# SCH_HackerCard_2024-08-18.net
KiCad netlist of a schematic drawn in EasyEDA
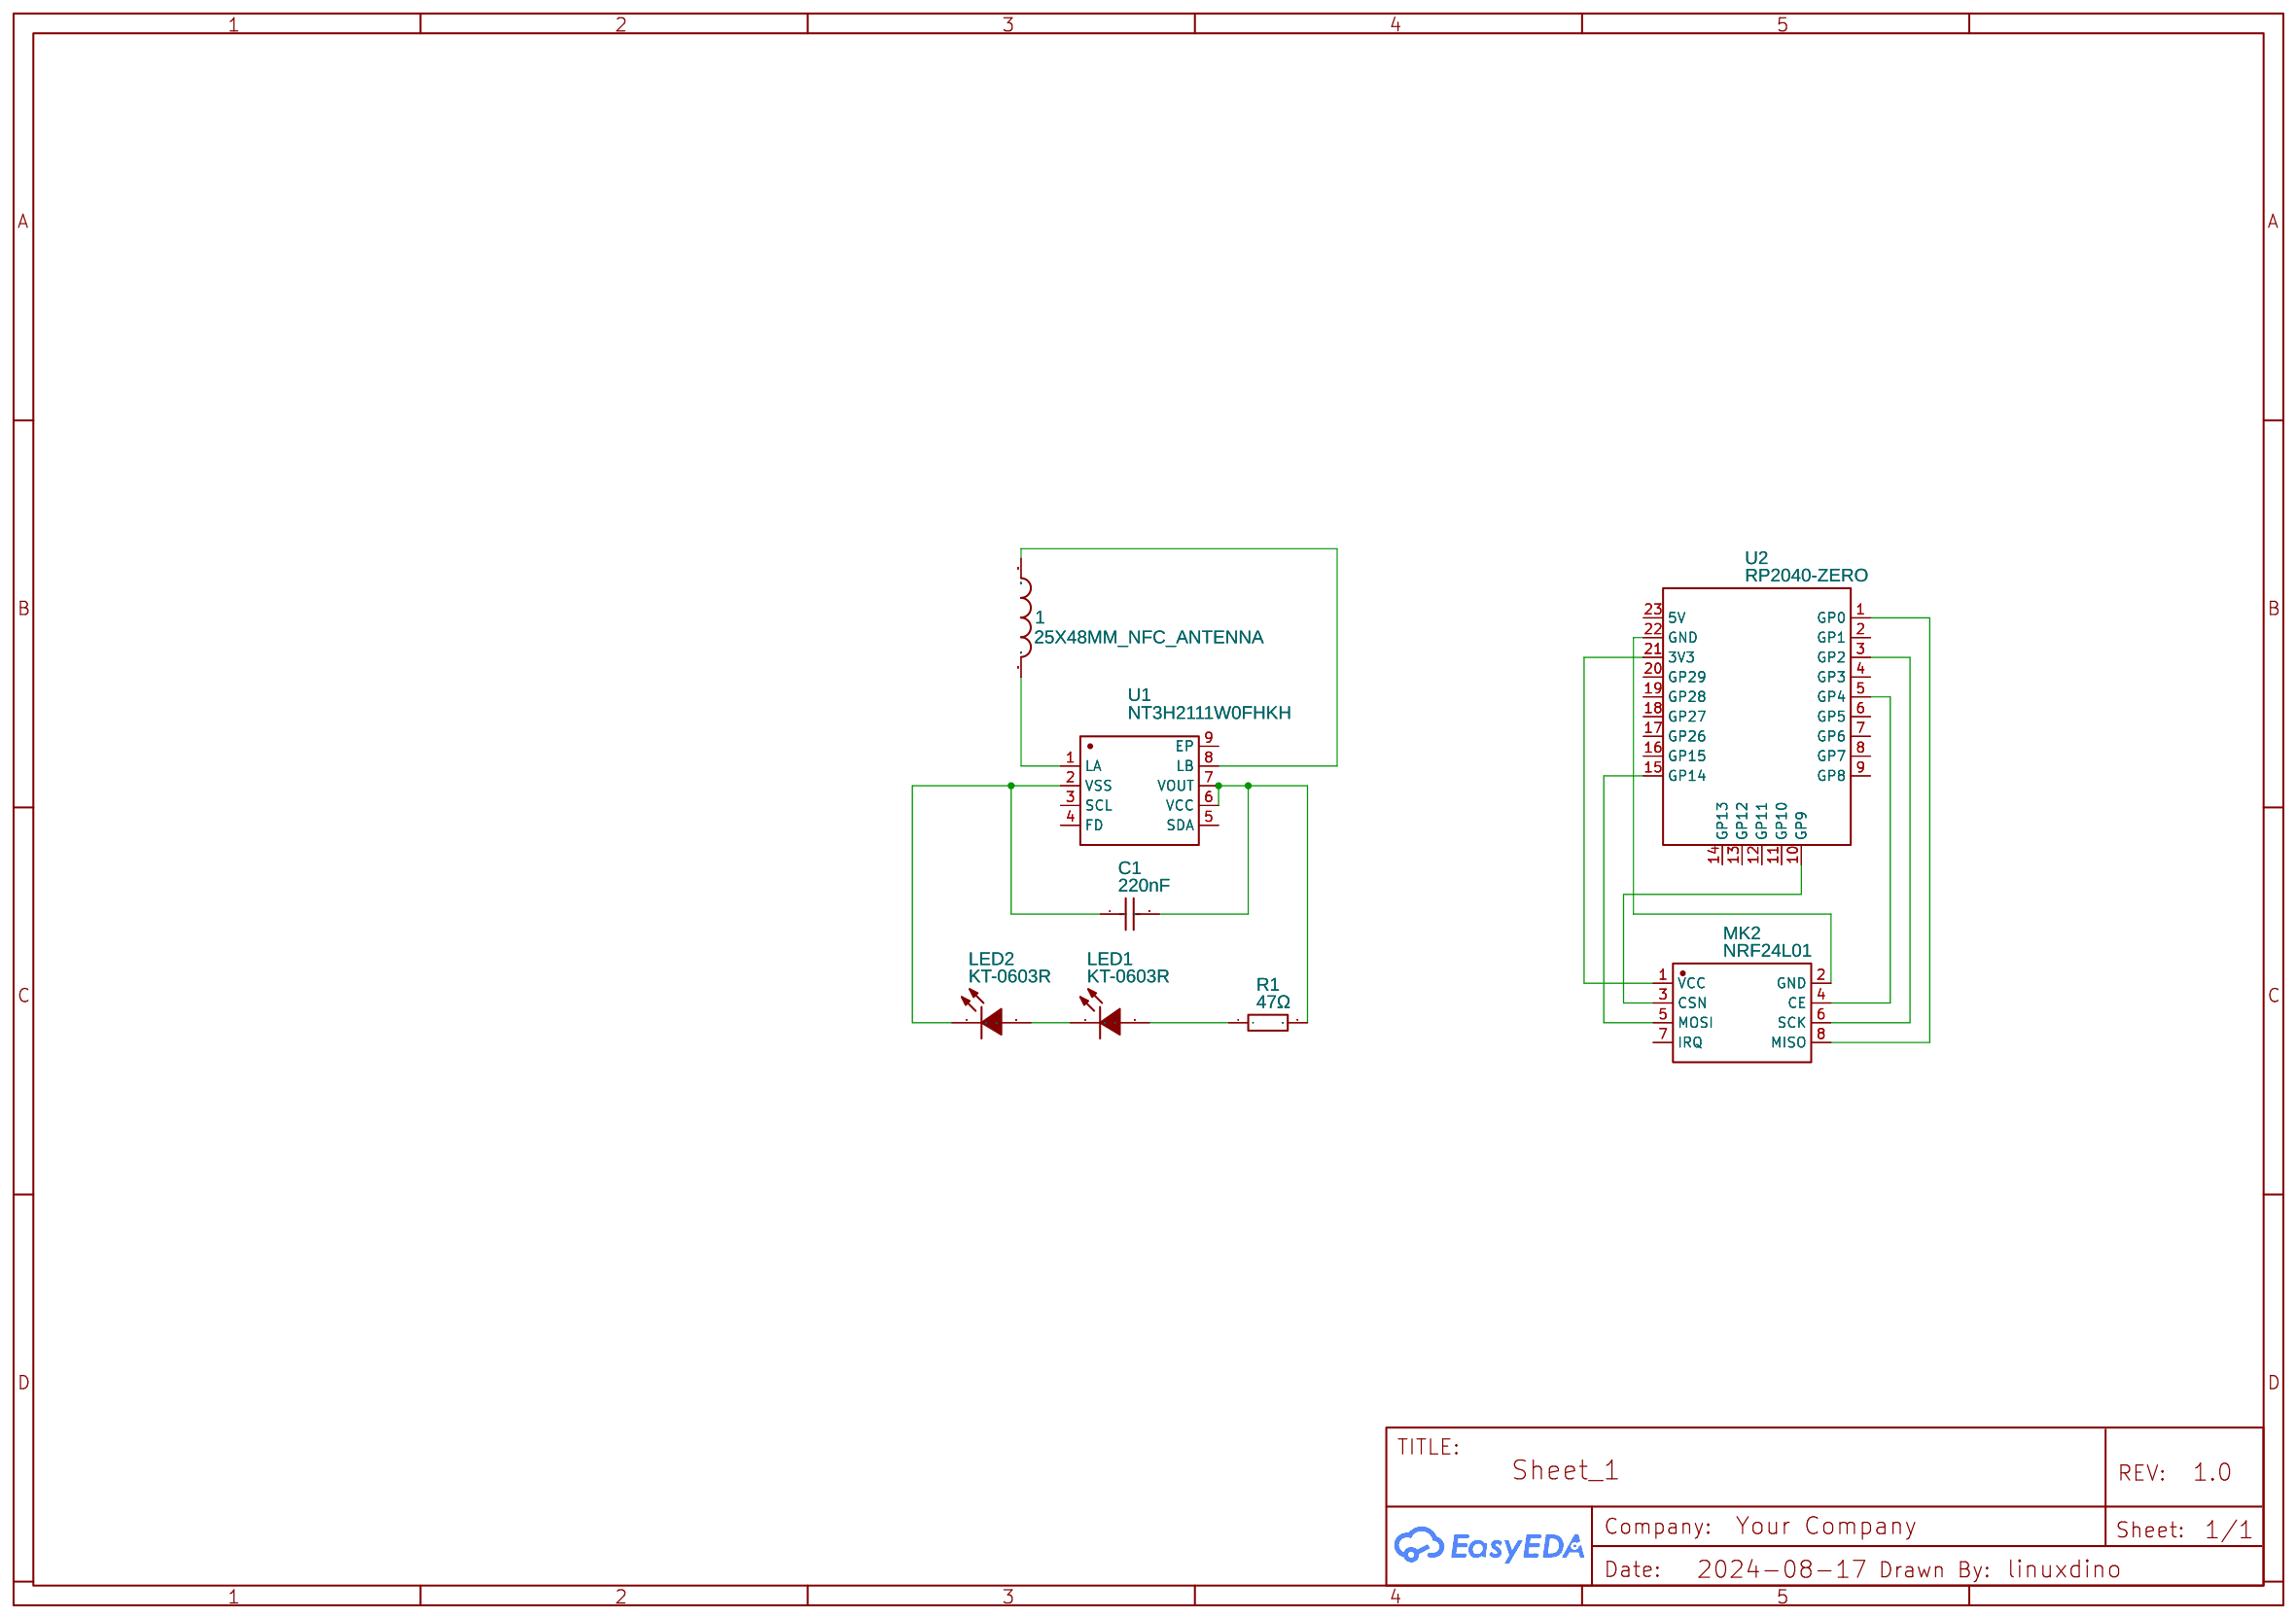
[diagram p0: schematic sheet]

(export (version "E")
  (design (tool "Eeschema 10.0.6"))
  (components
    (comp (ref "1") (value "25X48MM_NFC_ANTENNA") (libsource (lib "") (part "25X48MM_NFC_ANTENNA")))
    (comp (ref "C1")
      (value "220nF")
      (fields
        (field (name "Manufacturer Part") "CL10B224KA8NNNC")
        (field (name "Manufacturer") "SAMSUNG(三星)")
      )
      (libsource (lib "") (part "CL10B224KA8NNNC"))
    )
    (comp (ref "LED1")
      (value "KT-0603R")
      (fields (field (name "Manufacturer") "KENTO"))
      (libsource (lib "") (part "KT-0603R"))
    )
    (comp (ref "LED2")
      (value "KT-0603R")
      (fields (field (name "Manufacturer") "KENTO"))
      (libsource (lib "") (part "KT-0603R"))
    )
    (comp (ref "MK2")
      (value "NRF24L01")
      (fields (field (name "Manufacturer Part") "NF-04") (field (name "Manufacturer") "Ai-Thinker(安信可)"))
      (libsource (lib "") (part "NRF24L01"))
    )
    (comp (ref "R1")
      (value "47Ω")
      (fields
        (field (name "Manufacturer Part") "0603WAF470JT5E")
        (field (name "Manufacturer") "UNI-ROYAL(厚声)")
      )
      (libsource (lib "") (part "0603WAF470JT5E"))
    )
    (comp (ref "U1")
      (value "NT3H2111W0FHKH")
      (fields (field (name "Manufacturer") "NXP(恩智浦)"))
      (libsource (lib "") (part "NT3H2111W0FHKH"))
    )
    (comp (ref "U2")
      (value "RP2040-ZERO")
      (fields
        (field (name "Manufacturer Part") "RP2040-Zero")
        (field (name "Manufacturer") "Waveshare(微雪电子)")
      )
      (libsource (lib "") (part "RP2040-ZERO"))
    )
  )
  (nets
    (net (code "1") (name "Net-(LED1-A)") (class "Default")
      (node (ref "LED1") (pin "2") (pinfunction "A_2") (pintype "unspecified"))
      (node (ref "R1") (pin "1") (pinfunction "1_1") (pintype "input"))
    )
    (net (code "2") (name "Net-(LED1-K)") (class "Default")
      (node (ref "LED1") (pin "1") (pinfunction "K_1") (pintype "unspecified"))
      (node (ref "LED2") (pin "2") (pinfunction "A_2") (pintype "unspecified"))
    )
    (net (code "3") (name "Net-(LED2-K)") (class "Default")
      (node (ref "C1") (pin "1") (pinfunction "1_1") (pintype "input"))
      (node (ref "LED2") (pin "1") (pinfunction "K_1") (pintype "unspecified"))
      (node (ref "U1") (pin "2") (pinfunction "VSS_2") (pintype "unspecified"))
    )
    (net (code "4") (name "Net-(MK2-CE)") (class "Default")
      (node (ref "MK2") (pin "4") (pinfunction "CE_4") (pintype "unspecified"))
      (node (ref "U2") (pin "5") (pinfunction "GP4_5") (pintype "unspecified"))
    )
    (net (code "5") (name "Net-(MK2-CSN)") (class "Default")
      (node (ref "MK2") (pin "3") (pinfunction "CSN_3") (pintype "unspecified"))
      (node (ref "U2") (pin "10") (pinfunction "GP9_10") (pintype "unspecified"))
    )
    (net (code "6") (name "Net-(MK2-GND)") (class "Default")
      (node (ref "MK2") (pin "2") (pinfunction "GND_2") (pintype "unspecified"))
      (node (ref "U2") (pin "22") (pinfunction "GND_22") (pintype "unspecified"))
    )
    (net (code "7") (name "Net-(MK2-MISO)") (class "Default")
      (node (ref "MK2") (pin "8") (pinfunction "MISO_8") (pintype "unspecified"))
      (node (ref "U2") (pin "1") (pinfunction "GP0_1") (pintype "unspecified"))
    )
    (net (code "8") (name "Net-(MK2-MOSI)") (class "Default")
      (node (ref "MK2") (pin "5") (pinfunction "MOSI_5") (pintype "unspecified"))
      (node (ref "U2") (pin "15") (pinfunction "GP14_15") (pintype "unspecified"))
    )
    (net (code "9") (name "Net-(MK2-SCK)") (class "Default")
      (node (ref "MK2") (pin "6") (pinfunction "SCK_6") (pintype "unspecified"))
      (node (ref "U2") (pin "3") (pinfunction "GP2_3") (pintype "unspecified"))
    )
    (net (code "10") (name "Net-(MK2-VCC)") (class "Default")
      (node (ref "MK2") (pin "1") (pinfunction "VCC_1") (pintype "unspecified"))
      (node (ref "U2") (pin "21") (pinfunction "3V3_21") (pintype "unspecified"))
    )
    (net (code "11") (name "Net-(U1-LA)") (class "Default")
      (node (ref "1") (pin "P$2") (pinfunction "P$2_P$2") (pintype "bidirectional"))
      (node (ref "U1") (pin "1") (pinfunction "LA_1") (pintype "unspecified"))
    )
    (net (code "12") (name "Net-(U1-LB)") (class "Default")
      (node (ref "1") (pin "P$1") (pinfunction "P$1_P$1") (pintype "bidirectional"))
      (node (ref "U1") (pin "8") (pinfunction "LB_8") (pintype "unspecified"))
    )
    (net (code "13") (name "Net-(U1-VCC)") (class "Default")
      (node (ref "C1") (pin "2") (pinfunction "2_2") (pintype "input"))
      (node (ref "R1") (pin "2") (pinfunction "2_2") (pintype "input"))
      (node (ref "U1") (pin "6") (pinfunction "VCC_6") (pintype "unspecified"))
      (node (ref "U1") (pin "7") (pinfunction "VOUT_7") (pintype "unspecified"))
    )
    (net (code "14") (name "unconnected-(MK2-IRQ-Pad7)") (class "Default")
      (node (ref "MK2") (pin "7") (pinfunction "IRQ_7") (pintype "unspecified"))
    )
    (net (code "15") (name "unconnected-(U1-EP-Pad9)") (class "Default")
      (node (ref "U1") (pin "9") (pinfunction "EP_9") (pintype "unspecified"))
    )
    (net (code "16") (name "unconnected-(U1-FD-Pad4)") (class "Default")
      (node (ref "U1") (pin "4") (pinfunction "FD_4") (pintype "unspecified"))
    )
    (net (code "17") (name "unconnected-(U1-SCL-Pad3)") (class "Default")
      (node (ref "U1") (pin "3") (pinfunction "SCL_3") (pintype "unspecified"))
    )
    (net (code "18") (name "unconnected-(U1-SDA-Pad5)") (class "Default")
      (node (ref "U1") (pin "5") (pinfunction "SDA_5") (pintype "unspecified"))
    )
    (net (code "19") (name "unconnected-(U2-5V-Pad23)") (class "Default")
      (node (ref "U2") (pin "23") (pinfunction "5V_23") (pintype "unspecified"))
    )
    (net (code "20") (name "unconnected-(U2-GP1-Pad2)") (class "Default")
      (node (ref "U2") (pin "2") (pinfunction "GP1_2") (pintype "unspecified"))
    )
    (net (code "21") (name "unconnected-(U2-GP3-Pad4)") (class "Default")
      (node (ref "U2") (pin "4") (pinfunction "GP3_4") (pintype "unspecified"))
    )
    (net (code "22") (name "unconnected-(U2-GP5-Pad6)") (class "Default")
      (node (ref "U2") (pin "6") (pinfunction "GP5_6") (pintype "unspecified"))
    )
    (net (code "23") (name "unconnected-(U2-GP6-Pad7)") (class "Default")
      (node (ref "U2") (pin "7") (pinfunction "GP6_7") (pintype "unspecified"))
    )
    (net (code "24") (name "unconnected-(U2-GP7-Pad8)") (class "Default")
      (node (ref "U2") (pin "8") (pinfunction "GP7_8") (pintype "unspecified"))
    )
    (net (code "25") (name "unconnected-(U2-GP8-Pad9)") (class "Default")
      (node (ref "U2") (pin "9") (pinfunction "GP8_9") (pintype "unspecified"))
    )
    (net (code "26") (name "unconnected-(U2-GP10-Pad11)") (class "Default")
      (node (ref "U2") (pin "11") (pinfunction "GP10_11") (pintype "unspecified"))
    )
    (net (code "27") (name "unconnected-(U2-GP11-Pad12)") (class "Default")
      (node (ref "U2") (pin "12") (pinfunction "GP11_12") (pintype "unspecified"))
    )
    (net (code "28") (name "unconnected-(U2-GP12-Pad13)") (class "Default")
      (node (ref "U2") (pin "13") (pinfunction "GP12_13") (pintype "unspecified"))
    )
    (net (code "29") (name "unconnected-(U2-GP13-Pad14)") (class "Default")
      (node (ref "U2") (pin "14") (pinfunction "GP13_14") (pintype "unspecified"))
    )
    (net (code "30") (name "unconnected-(U2-GP15-Pad16)") (class "Default")
      (node (ref "U2") (pin "16") (pinfunction "GP15_16") (pintype "unspecified"))
    )
    (net (code "31") (name "unconnected-(U2-GP26-Pad17)") (class "Default")
      (node (ref "U2") (pin "17") (pinfunction "GP26_17") (pintype "unspecified"))
    )
    (net (code "32") (name "unconnected-(U2-GP27-Pad18)") (class "Default")
      (node (ref "U2") (pin "18") (pinfunction "GP27_18") (pintype "unspecified"))
    )
    (net (code "33") (name "unconnected-(U2-GP28-Pad19)") (class "Default")
      (node (ref "U2") (pin "19") (pinfunction "GP28_19") (pintype "unspecified"))
    )
    (net (code "34") (name "unconnected-(U2-GP29-Pad20)") (class "Default")
      (node (ref "U2") (pin "20") (pinfunction "GP29_20") (pintype "unspecified"))
    )
  )
)
